# BMW_F800GS_Board.net
KiCad netlist of a schematic drawn in Altium Designer
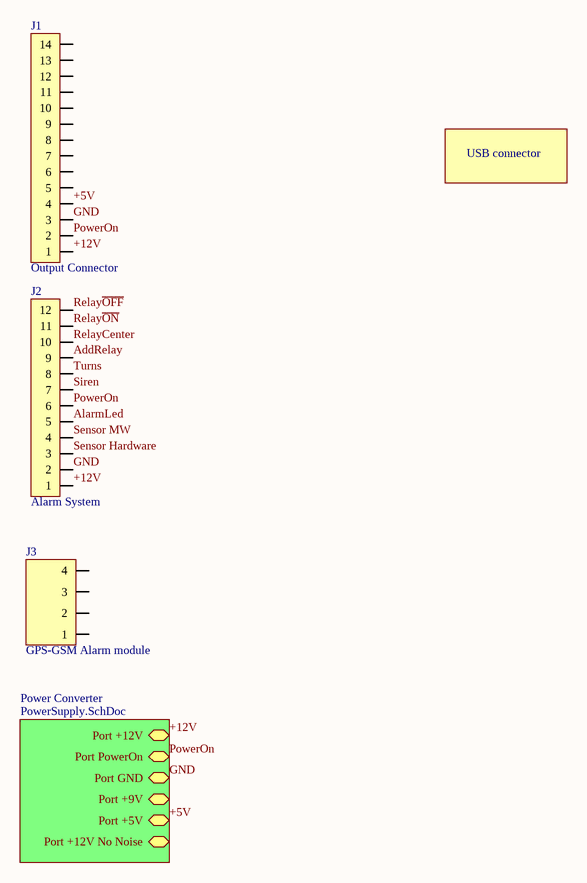
[diagram p0: BMW F800GS Board.SchDoc]

(export (version "E")
  (design (tool "Eeschema 10.0.6"))
  (components
    (comp (ref "J1")
      (value "Output Connector")
      (footprint "Connector:Molex Micro-Fit 3.0 - 14 pin D R")
      (description "Horisontal, Dbl line, Male")
      (libsource (lib "Connector") (part "Micro-Fit 14 (2x7)"))
    )
    (comp (ref "J2")
      (value "Alarm System")
      (footprint "Connector:Molex Micro-Fit 3.0 - 12 pin D R")
      (description "Horisontal, Dbl line, Male")
      (libsource (lib "Connector") (part "Micro-Fit 12 (2x6)"))
    )
    (comp (ref "J3")
      (value "GPS-GSM Alarm module")
      (footprint "Connector:Line 2.54 X 4")
      (description "Vert, Sgl line, Male")
      (libsource (lib "Connector") (part "PLS-4"))
    )
  )
  (nets
    (net (code "1") (name "/+5V") (class "Default")
      (node (ref "J1") (pin "4") (pinfunction "4_4") (pintype "passive"))
    )
    (net (code "2") (name "/+12V") (class "Default")
      (node (ref "J1") (pin "1") (pinfunction "1_1") (pintype "passive"))
      (node (ref "J2") (pin "1") (pinfunction "1_1") (pintype "passive"))
    )
    (net (code "3") (name "/AddRelay") (class "Default")
      (node (ref "J2") (pin "9") (pinfunction "9_9") (pintype "passive"))
    )
    (net (code "4") (name "/AlarmLed") (class "Default")
      (node (ref "J2") (pin "5") (pinfunction "5_5") (pintype "passive"))
    )
    (net (code "5") (name "/GND") (class "Default")
      (node (ref "J1") (pin "3") (pinfunction "3_3") (pintype "passive"))
      (node (ref "J2") (pin "2") (pinfunction "2_2") (pintype "passive"))
    )
    (net (code "8") (name "/PowerOn") (class "Default")
      (node (ref "J1") (pin "2") (pinfunction "2_2") (pintype "passive"))
      (node (ref "J2") (pin "6") (pinfunction "6_6") (pintype "passive"))
    )
    (net (code "9") (name "/RelayCenter") (class "Default")
      (node (ref "J2") (pin "10") (pinfunction "10_10") (pintype "passive"))
    )
    (net (code "10") (name "/Relay~{OFF}") (class "Default")
      (node (ref "J2") (pin "12") (pinfunction "12_12") (pintype "passive"))
    )
    (net (code "11") (name "/Relay~{ON}") (class "Default")
      (node (ref "J2") (pin "11") (pinfunction "11_11") (pintype "passive"))
    )
    (net (code "12") (name "/Sensor Hardware") (class "Default")
      (node (ref "J2") (pin "3") (pinfunction "3_3") (pintype "passive"))
    )
    (net (code "13") (name "/Sensor MW") (class "Default")
      (node (ref "J2") (pin "4") (pinfunction "4_4") (pintype "passive"))
    )
    (net (code "14") (name "/Siren") (class "Default")
      (node (ref "J2") (pin "7") (pinfunction "7_7") (pintype "passive"))
    )
    (net (code "15") (name "/Turns") (class "Default")
      (node (ref "J2") (pin "8") (pinfunction "8_8") (pintype "passive"))
    )
    (net (code "16") (name "unconnected-(J1-Pad5)") (class "Default")
      (node (ref "J1") (pin "5") (pinfunction "5_5") (pintype "passive"))
    )
    (net (code "17") (name "unconnected-(J1-Pad6)") (class "Default")
      (node (ref "J1") (pin "6") (pinfunction "6_6") (pintype "passive"))
    )
    (net (code "18") (name "unconnected-(J1-Pad7)") (class "Default")
      (node (ref "J1") (pin "7") (pinfunction "7_7") (pintype "passive"))
    )
    (net (code "19") (name "unconnected-(J1-Pad8)") (class "Default")
      (node (ref "J1") (pin "8") (pinfunction "8_8") (pintype "passive"))
    )
    (net (code "20") (name "unconnected-(J1-Pad9)") (class "Default")
      (node (ref "J1") (pin "9") (pinfunction "9_9") (pintype "passive"))
    )
    (net (code "21") (name "unconnected-(J1-Pad10)") (class "Default")
      (node (ref "J1") (pin "10") (pinfunction "10_10") (pintype "passive"))
    )
    (net (code "22") (name "unconnected-(J1-Pad11)") (class "Default")
      (node (ref "J1") (pin "11") (pinfunction "11_11") (pintype "passive"))
    )
    (net (code "23") (name "unconnected-(J1-Pad12)") (class "Default")
      (node (ref "J1") (pin "12") (pinfunction "12_12") (pintype "passive"))
    )
    (net (code "24") (name "unconnected-(J1-Pad13)") (class "Default")
      (node (ref "J1") (pin "13") (pinfunction "13_13") (pintype "passive"))
    )
    (net (code "25") (name "unconnected-(J1-Pad14)") (class "Default")
      (node (ref "J1") (pin "14") (pinfunction "14_14") (pintype "passive"))
    )
    (net (code "26") (name "unconnected-(J3-Pad1)") (class "Default")
      (node (ref "J3") (pin "1") (pinfunction "1_1") (pintype "passive"))
    )
    (net (code "27") (name "unconnected-(J3-Pad2)") (class "Default")
      (node (ref "J3") (pin "2") (pinfunction "2_2") (pintype "passive"))
    )
    (net (code "28") (name "unconnected-(J3-Pad3)") (class "Default")
      (node (ref "J3") (pin "3") (pinfunction "3_3") (pintype "passive"))
    )
    (net (code "29") (name "unconnected-(J3-Pad4)") (class "Default")
      (node (ref "J3") (pin "4") (pinfunction "4_4") (pintype "passive"))
    )
  )
)
